# LED_MEM.net
KiCad netlist of a schematic drawn in Altium Designer
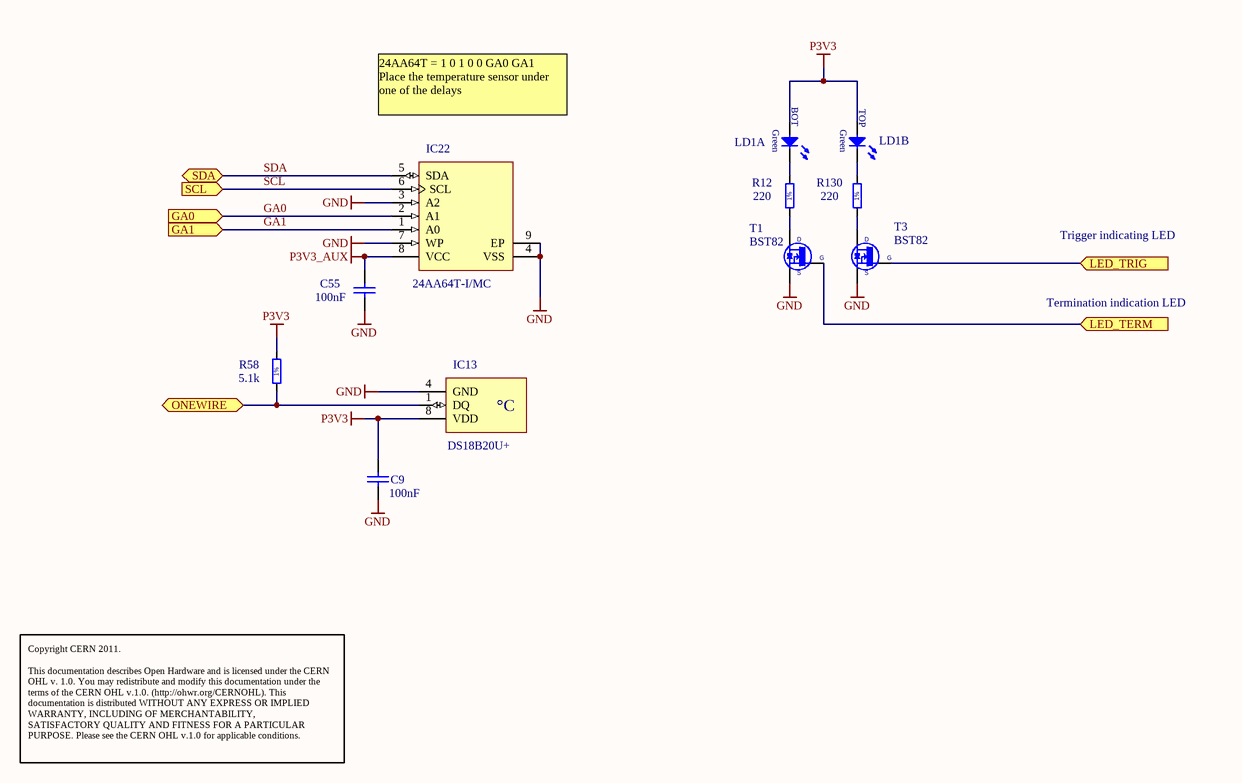
[diagram p0: LED_MEM.SchDoc]

(export (version "E")
  (design (tool "Eeschema 10.0.6"))
  (components
    (comp (ref "C9")
      (value "100nF")
      (footprint "CAPC1608X87N")
      (description "Non-polarised capacitor")
      (fields
        (field (name "PART NUMBER") "CC0603_100NF_50V_10%_X7R")
        (field (name "VOLTAGE") "50V")
        (field (name "AUTHOR") "CERN DEM JLC")
      )
      (libsource (lib "Capacitors") (part "Capacitor - non polarized"))
    )
    (comp (ref "C55")
      (value "100nF")
      (footprint "CAPC1608X87N")
      (description "Non-polarised capacitor")
      (fields
        (field (name "PART NUMBER") "CC0603_100NF_50V_10%_X7R")
        (field (name "VOLTAGE") "50V")
        (field (name "AUTHOR") "CERN DEM JLC")
      )
      (libsource (lib "Capacitors") (part "Capacitor - non polarized"))
    )
    (comp (ref "IC13")
      (value "DS18B20U+")
      (footprint "SOP65P490X110-8N")
      (description "Programmable Resolution 1-Wire Digital Thermometer")
      (fields (field (name "MANUFACTURER") "DALLAS MAXIM") (field (name "AUTHOR") "CERN DEM JLC"))
      (libsource (lib "ICs And Semiconductors") (part "DS18B20U+"))
    )
    (comp (ref "IC22")
      (value "24AA64T-I/MC")
      (footprint "SON50P300X200X100-9N-S175X155")
      (description "1.7-5.5V 64K I2C Serial EEPROM")
      (fields (field (name "MANUFACTURER") "MICROCHIP TECHNOLOGY") (field (name "AUTHOR") "CERN DEM JLC"))
      (libsource (lib "ICs And Semiconductors") (part "24AA64T-I/MC"))
    )
    (comp (ref "LD1")
      (value "Green/Green")
      (footprint "LED_DIALIGHT_571-0122-100F")
      (description "LED x2 Green 1C2A-BOT_3C4A-TOP")
      (fields
        (field (name "PART NUMBER") "LED_DIALIGHT_571-0122-100F")
        (field (name "MANUFACTURER") "DIALIGHT")
        (field (name "AUTHOR") "CERN DEM JLC")
      )
      (libsource (lib "ICs And Semiconductors") (part "LED x2 Green 1C2A-BOT_3C4A-TOP"))
    )
    (comp (ref "R12")
      (value "220")
      (footprint "RESC1608X55N")
      (description "Resistor - 1%")
      (fields
        (field (name "PART NUMBER") "R0603_220R_1%_0.1W_100PPM")
        (field (name "POWER") "0.1W")
        (field (name "AUTHOR") "CERN DEM JLC")
      )
      (libsource (lib "Resistors") (part "Resistor - 1%"))
    )
    (comp (ref "R58")
      (value "5.1k")
      (footprint "RESC1608X55N")
      (description "Resistor - 1%")
      (fields
        (field (name "PART NUMBER") "R0603_5K1_1%_0.1W_100PPM")
        (field (name "POWER") "0.1W")
        (field (name "AUTHOR") "CERN DEM JLC")
      )
      (libsource (lib "Resistors") (part "Resistor - 1%"))
    )
    (comp (ref "R130")
      (value "220")
      (footprint "RESC1608X55N")
      (description "Resistor - 1%")
      (fields
        (field (name "PART NUMBER") "R0603_220R_1%_0.1W_100PPM")
        (field (name "POWER") "0.1W")
        (field (name "AUTHOR") "CERN DEM JLC")
      )
      (libsource (lib "Resistors") (part "Resistor - 1%"))
    )
    (comp (ref "T1")
      (value "BST82")
      (footprint "SOT95P240X110-3N")
      (description "N-CHANNEL MOSFET WITH DIODE")
      (fields (field (name "MANUFACTURER") "NXP SEMICONDUCTORS") (field (name "AUTHOR") "CERN DEM JLC"))
      (libsource (lib "ICs And Semiconductors") (part "N-MOSFET-D 1G 2S 3D"))
    )
    (comp (ref "T3")
      (value "BST82")
      (footprint "SOT95P240X110-3N")
      (description "N-CHANNEL MOSFET WITH DIODE")
      (fields (field (name "MANUFACTURER") "NXP SEMICONDUCTORS") (field (name "AUTHOR") "CERN DEM JLC"))
      (libsource (lib "ICs And Semiconductors") (part "N-MOSFET-D 1G 2S 3D"))
    )
  )
  (nets
    (net (code "1") (name "/GA0") (class "Default")
      (node (ref "IC22") (pin "2") (pinfunction "A1_2") (pintype "input"))
    )
    (net (code "2") (name "/GA1") (class "Default")
      (node (ref "IC22") (pin "1") (pinfunction "A0_1") (pintype "input"))
    )
    (net (code "3") (name "/LED_TERM") (class "Default")
      (node (ref "T1") (pin "1") (pinfunction "G_1") (pintype "passive"))
    )
    (net (code "4") (name "/LED_TRIG") (class "Default")
      (node (ref "T3") (pin "1") (pinfunction "G_1") (pintype "passive"))
    )
    (net (code "5") (name "/ONEWIRE") (class "Default")
      (node (ref "IC13") (pin "1") (pinfunction "DQ_1") (pintype "bidirectional"))
      (node (ref "R58") (pin "1") (pinfunction "1_1") (pintype "passive"))
    )
    (net (code "6") (name "/SCL") (class "Default")
      (node (ref "IC22") (pin "6") (pinfunction "SCL_6") (pintype "input"))
    )
    (net (code "7") (name "/SDA") (class "Default")
      (node (ref "IC22") (pin "5") (pinfunction "SDA_5") (pintype "bidirectional"))
    )
    (net (code "8") (name "GND") (class "Default")
      (node (ref "C55") (pin "2") (pinfunction "2_2") (pintype "passive"))
      (node (ref "C9") (pin "2") (pinfunction "2_2") (pintype "passive"))
      (node (ref "IC13") (pin "4") (pinfunction "GND_4") (pintype "power_in"))
      (node (ref "IC22") (pin "3") (pinfunction "A2_3") (pintype "input"))
      (node (ref "IC22") (pin "4") (pinfunction "VSS_4") (pintype "power_in"))
      (node (ref "IC22") (pin "7") (pinfunction "WP_7") (pintype "input"))
      (node (ref "IC22") (pin "9") (pinfunction "EP_9") (pintype "power_in"))
      (node (ref "T1") (pin "2") (pinfunction "S_2") (pintype "passive"))
      (node (ref "T3") (pin "2") (pinfunction "S_2") (pintype "passive"))
    )
    (net (code "9") (name "Net-(LD1A-C)") (class "Default")
      (node (ref "LD1") (pin "1") (pinfunction "C_1") (pintype "passive"))
      (node (ref "R12") (pin "2") (pinfunction "2_2") (pintype "passive"))
    )
    (net (code "10") (name "Net-(LD1B-C)") (class "Default")
      (node (ref "LD1") (pin "3") (pinfunction "C_3") (pintype "passive"))
      (node (ref "R130") (pin "2") (pinfunction "2_2") (pintype "passive"))
    )
    (net (code "11") (name "Net-(T1-D)") (class "Default")
      (node (ref "R12") (pin "1") (pinfunction "1_1") (pintype "passive"))
      (node (ref "T1") (pin "3") (pinfunction "D_3") (pintype "passive"))
    )
    (net (code "12") (name "Net-(T3-D)") (class "Default")
      (node (ref "R130") (pin "1") (pinfunction "1_1") (pintype "passive"))
      (node (ref "T3") (pin "3") (pinfunction "D_3") (pintype "passive"))
    )
    (net (code "13") (name "P3V3") (class "Default")
      (node (ref "C9") (pin "1") (pinfunction "1_1") (pintype "passive"))
      (node (ref "IC13") (pin "8") (pinfunction "VDD_8") (pintype "power_in"))
      (node (ref "LD1") (pin "2") (pinfunction "A_2") (pintype "passive"))
      (node (ref "LD1") (pin "4") (pinfunction "A_4") (pintype "passive"))
      (node (ref "R58") (pin "2") (pinfunction "2_2") (pintype "passive"))
    )
    (net (code "14") (name "P3V3_AUX") (class "Default")
      (node (ref "C55") (pin "1") (pinfunction "1_1") (pintype "passive"))
      (node (ref "IC22") (pin "8") (pinfunction "VCC_8") (pintype "power_in"))
    )
  )
)
